# ESP32.net
KiCad netlist of a schematic drawn in Altium Designer
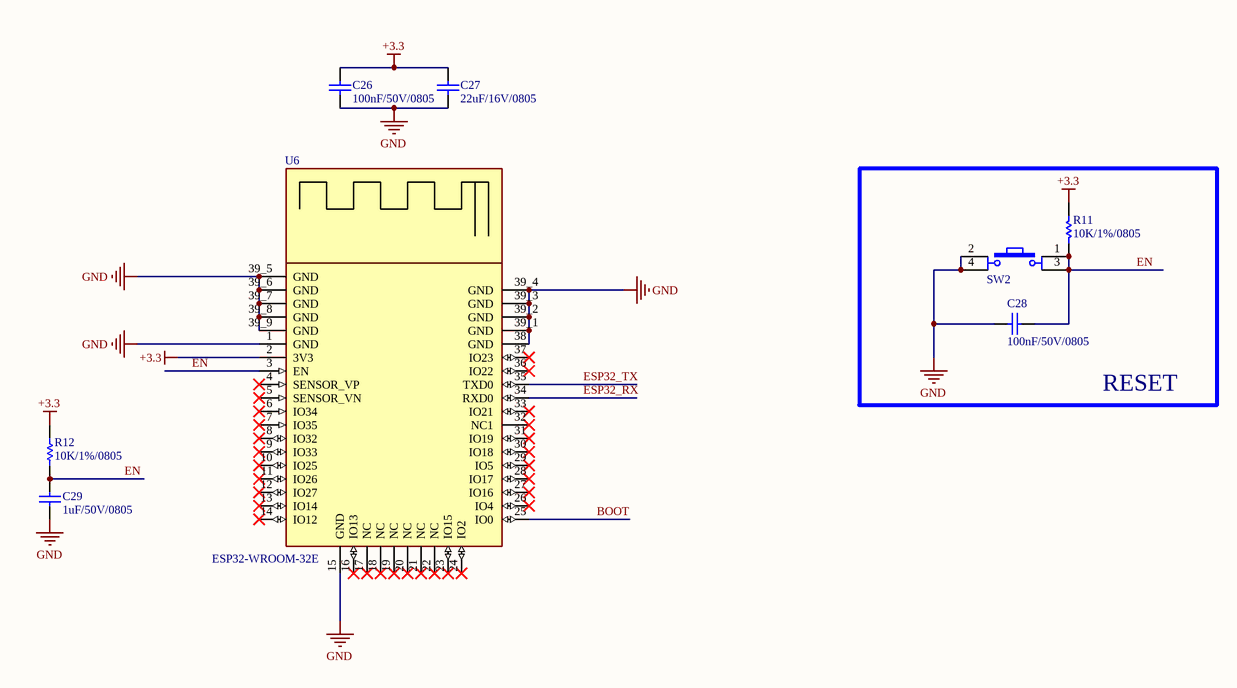
[diagram p0: ESP32.SchDoc]

(export (version "E")
  (design (tool "Eeschema 10.0.6"))
  (components
    (comp (ref "C26")
      (value "100nF/50V/0805")
      (footprint "CAP-SM-0805")
      (description "Capacitor")
      (fields (field (name "Comment") "Cap Non-Pol SMD"))
      (libsource (lib "PIF_Library") (part "Cap Non-Pol SMD"))
    )
    (comp (ref "C27")
      (value "22uF/16V/0805")
      (footprint "CAP-SM-0805")
      (description "Capacitor")
      (fields (field (name "Comment") "Cap Non-Pol SMD"))
      (libsource (lib "PIF_Library") (part "Cap Non-Pol SMD"))
    )
    (comp (ref "C28")
      (value "100nF/50V/0805")
      (footprint "CAP-SM-0805")
      (description "Capacitor")
      (fields (field (name "Comment") "Cap Non-Pol SMD"))
      (libsource (lib "PIF_Library") (part "Cap Non-Pol SMD"))
    )
    (comp (ref "C29")
      (value "1uF/50V/0805")
      (footprint "CAP-SM-0805")
      (description "Capacitor")
      (fields (field (name "Comment") "Cap Non-Pol SMD"))
      (libsource (lib "PIF_Library") (part "Cap Non-Pol SMD"))
    )
    (comp (ref "R11")
      (value "10K/1%/0805")
      (footprint "RES-SM-0805")
      (description "Resistor")
      (fields (field (name "Comment") "RESISTOR SMD"))
      (libsource (lib "PIF_Library") (part "RESISTOR SMD"))
    )
    (comp (ref "R12")
      (value "10K/1%/0805")
      (footprint "RES-SM-0805")
      (description "Resistor")
      (fields (field (name "Comment") "RESISTOR SMD"))
      (libsource (lib "PIF_Library") (part "RESISTOR SMD"))
    )
    (comp (ref "SW2")
      (value "SW")
      (footprint "Tact SW 4 pin")
      (description "Switch button 4 pin")
      (libsource (lib "PIF_Library") (part "Tact SW - 4Pin"))
    )
    (comp (ref "U6")
      (value "ESP32-WROOM-32E")
      (footprint "ESP32-WROOM-32E")
      (libsource (lib "Giang's Libs") (part "ESP32-WROOM-32E"))
    )
  )
  (nets
    (net (code "1") (name "+3.3") (class "Default")
      (node (ref "C26") (pin "1") (pinfunction "1_1") (pintype "passive"))
      (node (ref "C27") (pin "1") (pinfunction "1_1") (pintype "passive"))
      (node (ref "R11") (pin "2") (pinfunction "2_2") (pintype "passive"))
      (node (ref "R12") (pin "2") (pinfunction "2_2") (pintype "passive"))
      (node (ref "U6") (pin "2") (pinfunction "3V3_2") (pintype "power_in"))
    )
    (net (code "2") (name "/BOOT") (class "Default")
      (node (ref "U6") (pin "25") (pinfunction "IO0_25") (pintype "bidirectional"))
    )
    (net (code "3") (name "/EN") (class "Default")
      (node (ref "C28") (pin "1") (pinfunction "1_1") (pintype "passive"))
      (node (ref "C29") (pin "2") (pinfunction "2_2") (pintype "passive"))
      (node (ref "R11") (pin "1") (pinfunction "1_1") (pintype "passive"))
      (node (ref "R12") (pin "1") (pinfunction "1_1") (pintype "passive"))
      (node (ref "SW2") (pin "1") (pintype "passive"))
      (node (ref "SW2") (pin "3") (pintype "passive"))
      (node (ref "U6") (pin "3") (pinfunction "EN_3") (pintype "input"))
    )
    (net (code "4") (name "/ESP32_RX") (class "Default")
      (node (ref "U6") (pin "34") (pinfunction "RXD0_34") (pintype "bidirectional"))
    )
    (net (code "5") (name "/ESP32_TX") (class "Default")
      (node (ref "U6") (pin "35") (pinfunction "TXD0_35") (pintype "bidirectional"))
    )
    (net (code "6") (name "GND") (class "Default")
      (node (ref "C26") (pin "2") (pinfunction "2_2") (pintype "passive"))
      (node (ref "C27") (pin "2") (pinfunction "2_2") (pintype "passive"))
      (node (ref "C28") (pin "2") (pinfunction "2_2") (pintype "passive"))
      (node (ref "C29") (pin "1") (pinfunction "1_1") (pintype "passive"))
      (node (ref "SW2") (pin "2") (pintype "passive"))
      (node (ref "SW2") (pin "4") (pintype "passive"))
      (node (ref "U6") (pin "1") (pinfunction "GND_1") (pintype "power_in"))
      (node (ref "U6") (pin "15") (pinfunction "GND_15") (pintype "power_in"))
      (node (ref "U6") (pin "38") (pinfunction "GND_38") (pintype "power_in"))
      (node (ref "U6") (pin "39_1") (pinfunction "GND_39_1") (pintype "power_in"))
      (node (ref "U6") (pin "39_2") (pinfunction "GND_39_2") (pintype "power_in"))
      (node (ref "U6") (pin "39_3") (pinfunction "GND_39_3") (pintype "power_in"))
      (node (ref "U6") (pin "39_4") (pinfunction "GND_39_4") (pintype "power_in"))
      (node (ref "U6") (pin "39_5") (pinfunction "GND_39_5") (pintype "power_in"))
      (node (ref "U6") (pin "39_6") (pinfunction "GND_39_6") (pintype "power_in"))
      (node (ref "U6") (pin "39_7") (pinfunction "GND_39_7") (pintype "power_in"))
      (node (ref "U6") (pin "39_8") (pinfunction "GND_39_8") (pintype "power_in"))
      (node (ref "U6") (pin "39_9") (pinfunction "GND_39_9") (pintype "power_in"))
    )
    (net (code "7") (name "unconnected-(U6-IO2-Pad24)") (class "Default")
      (node (ref "U6") (pin "24") (pinfunction "IO2_24") (pintype "bidirectional+no_connect"))
    )
    (net (code "8") (name "unconnected-(U6-IO4-Pad26)") (class "Default")
      (node (ref "U6") (pin "26") (pinfunction "IO4_26") (pintype "bidirectional+no_connect"))
    )
    (net (code "9") (name "unconnected-(U6-IO5-Pad29)") (class "Default")
      (node (ref "U6") (pin "29") (pinfunction "IO5_29") (pintype "bidirectional+no_connect"))
    )
    (net (code "10") (name "unconnected-(U6-IO12-Pad14)") (class "Default")
      (node (ref "U6") (pin "14") (pinfunction "IO12_14") (pintype "bidirectional+no_connect"))
    )
    (net (code "11") (name "unconnected-(U6-IO13-Pad16)") (class "Default")
      (node (ref "U6") (pin "16") (pinfunction "IO13_16") (pintype "bidirectional+no_connect"))
    )
    (net (code "12") (name "unconnected-(U6-IO14-Pad13)") (class "Default")
      (node (ref "U6") (pin "13") (pinfunction "IO14_13") (pintype "bidirectional+no_connect"))
    )
    (net (code "13") (name "unconnected-(U6-IO15-Pad23)") (class "Default")
      (node (ref "U6") (pin "23") (pinfunction "IO15_23") (pintype "bidirectional+no_connect"))
    )
    (net (code "14") (name "unconnected-(U6-IO16-Pad27)") (class "Default")
      (node (ref "U6") (pin "27") (pinfunction "IO16_27") (pintype "bidirectional+no_connect"))
    )
    (net (code "15") (name "unconnected-(U6-IO17-Pad28)") (class "Default")
      (node (ref "U6") (pin "28") (pinfunction "IO17_28") (pintype "bidirectional+no_connect"))
    )
    (net (code "16") (name "unconnected-(U6-IO18-Pad30)") (class "Default")
      (node (ref "U6") (pin "30") (pinfunction "IO18_30") (pintype "bidirectional+no_connect"))
    )
    (net (code "17") (name "unconnected-(U6-IO19-Pad31)") (class "Default")
      (node (ref "U6") (pin "31") (pinfunction "IO19_31") (pintype "bidirectional+no_connect"))
    )
    (net (code "18") (name "unconnected-(U6-IO21-Pad33)") (class "Default")
      (node (ref "U6") (pin "33") (pinfunction "IO21_33") (pintype "bidirectional+no_connect"))
    )
    (net (code "19") (name "unconnected-(U6-IO22-Pad36)") (class "Default")
      (node (ref "U6") (pin "36") (pinfunction "IO22_36") (pintype "bidirectional+no_connect"))
    )
    (net (code "20") (name "unconnected-(U6-IO23-Pad37)") (class "Default")
      (node (ref "U6") (pin "37") (pinfunction "IO23_37") (pintype "bidirectional+no_connect"))
    )
    (net (code "21") (name "unconnected-(U6-IO25-Pad10)") (class "Default")
      (node (ref "U6") (pin "10") (pinfunction "IO25_10") (pintype "bidirectional+no_connect"))
    )
    (net (code "22") (name "unconnected-(U6-IO26-Pad11)") (class "Default")
      (node (ref "U6") (pin "11") (pinfunction "IO26_11") (pintype "bidirectional+no_connect"))
    )
    (net (code "23") (name "unconnected-(U6-IO27-Pad12)") (class "Default")
      (node (ref "U6") (pin "12") (pinfunction "IO27_12") (pintype "bidirectional+no_connect"))
    )
    (net (code "24") (name "unconnected-(U6-IO32-Pad8)") (class "Default")
      (node (ref "U6") (pin "8") (pinfunction "IO32_8") (pintype "bidirectional+no_connect"))
    )
    (net (code "25") (name "unconnected-(U6-IO33-Pad9)") (class "Default")
      (node (ref "U6") (pin "9") (pinfunction "IO33_9") (pintype "bidirectional+no_connect"))
    )
    (net (code "26") (name "unconnected-(U6-IO34-Pad6)") (class "Default")
      (node (ref "U6") (pin "6") (pinfunction "IO34_6") (pintype "input+no_connect"))
    )
    (net (code "27") (name "unconnected-(U6-IO35-Pad7)") (class "Default")
      (node (ref "U6") (pin "7") (pinfunction "IO35_7") (pintype "input+no_connect"))
    )
    (net (code "28") (name "unconnected-(U6-NC-Pad17)") (class "Default")
      (node (ref "U6") (pin "17") (pinfunction "NC_17") (pintype "passive+no_connect"))
    )
    (net (code "29") (name "unconnected-(U6-NC-Pad18)") (class "Default")
      (node (ref "U6") (pin "18") (pinfunction "NC_18") (pintype "passive+no_connect"))
    )
    (net (code "30") (name "unconnected-(U6-NC-Pad19)") (class "Default")
      (node (ref "U6") (pin "19") (pinfunction "NC_19") (pintype "passive+no_connect"))
    )
    (net (code "31") (name "unconnected-(U6-NC-Pad20)") (class "Default")
      (node (ref "U6") (pin "20") (pinfunction "NC_20") (pintype "passive+no_connect"))
    )
    (net (code "32") (name "unconnected-(U6-NC-Pad21)") (class "Default")
      (node (ref "U6") (pin "21") (pinfunction "NC_21") (pintype "passive+no_connect"))
    )
    (net (code "33") (name "unconnected-(U6-NC-Pad22)") (class "Default")
      (node (ref "U6") (pin "22") (pinfunction "NC_22") (pintype "passive+no_connect"))
    )
    (net (code "34") (name "unconnected-(U6-NC1-Pad32)") (class "Default")
      (node (ref "U6") (pin "32") (pinfunction "NC1_32") (pintype "passive+no_connect"))
    )
    (net (code "35") (name "unconnected-(U6-SENSOR_VN-Pad5)") (class "Default")
      (node (ref "U6") (pin "5") (pinfunction "SENSOR_VN_5") (pintype "input+no_connect"))
    )
    (net (code "36") (name "unconnected-(U6-SENSOR_VP-Pad4)") (class "Default")
      (node (ref "U6") (pin "4") (pinfunction "SENSOR_VP_4") (pintype "input+no_connect"))
    )
  )
)
